# main_16.net
KiCad netlist of a schematic drawn in EAGLE
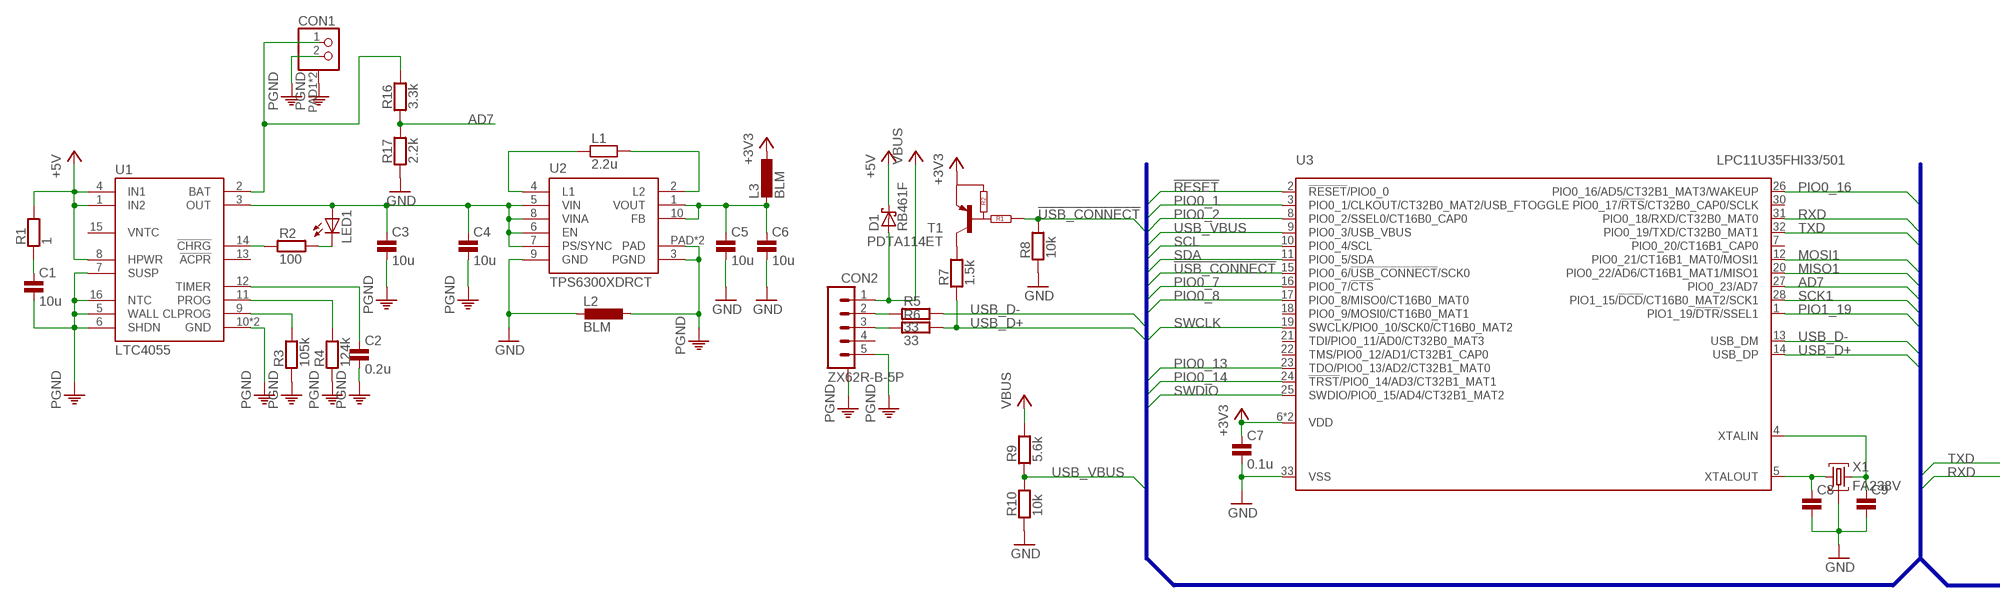
[diagram p0: schematic, sheet 1, part 1 of 2]
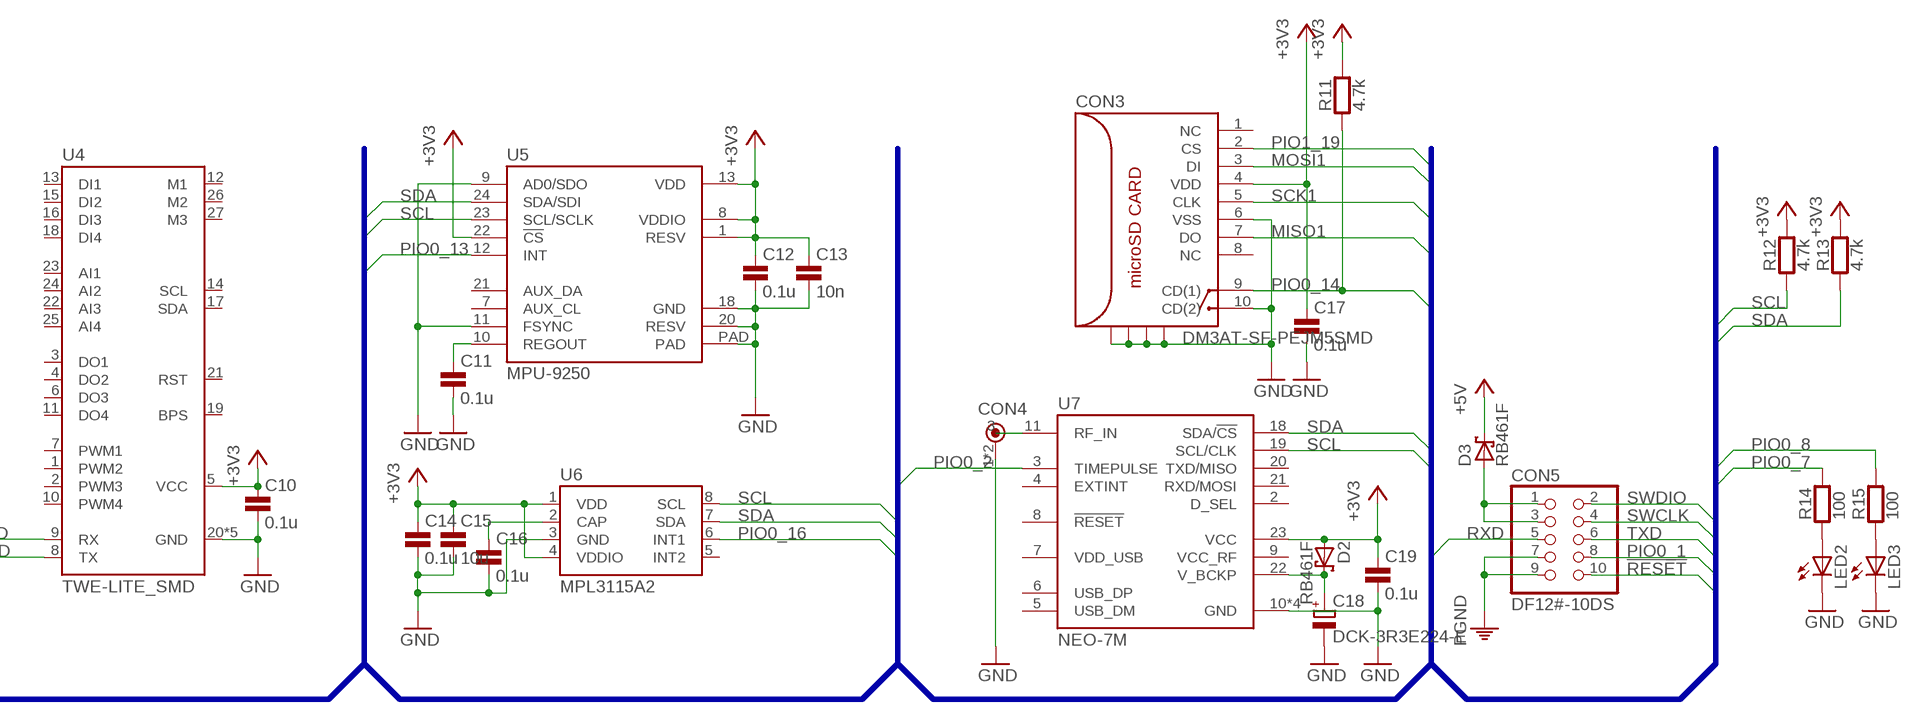
[diagram p1: schematic, sheet 1, part 2 of 2]

(export (version "E")
  (design (tool "Eeschema 10.0.6"))
  (components
    (comp (ref "C1")
      (value "10u")
      (footprint "eagle-import:0603")
      (libsource (lib "eagle-import") (part "C0603"))
    )
    (comp (ref "C2")
      (value "0.2u")
      (footprint "eagle-import:0402")
      (libsource (lib "eagle-import") (part "C0402"))
    )
    (comp (ref "C3")
      (value "10u")
      (footprint "eagle-import:0603")
      (libsource (lib "eagle-import") (part "C0603"))
    )
    (comp (ref "C4")
      (value "10u")
      (footprint "eagle-import:0603")
      (libsource (lib "eagle-import") (part "C0603"))
    )
    (comp (ref "C5")
      (value "10u")
      (footprint "eagle-import:0603")
      (libsource (lib "eagle-import") (part "C0603"))
    )
    (comp (ref "C6")
      (value "10u")
      (footprint "eagle-import:0603")
      (libsource (lib "eagle-import") (part "C0603"))
    )
    (comp (ref "C7")
      (value "0.1u")
      (footprint "eagle-import:0402")
      (libsource (lib "eagle-import") (part "C0402"))
    )
    (comp (ref "C8")
      (value "C0402")
      (footprint "eagle-import:0402")
      (libsource (lib "eagle-import") (part "C0402"))
    )
    (comp (ref "C9")
      (value "C0402")
      (footprint "eagle-import:0402")
      (libsource (lib "eagle-import") (part "C0402"))
    )
    (comp (ref "C10")
      (value "0.1u")
      (footprint "eagle-import:0402")
      (libsource (lib "eagle-import") (part "C0402"))
    )
    (comp (ref "C11")
      (value "0.1u")
      (footprint "eagle-import:0402")
      (libsource (lib "eagle-import") (part "C0402"))
    )
    (comp (ref "C12")
      (value "0.1u")
      (footprint "eagle-import:0402")
      (libsource (lib "eagle-import") (part "C0402"))
    )
    (comp (ref "C13")
      (value "10n")
      (footprint "eagle-import:0402")
      (libsource (lib "eagle-import") (part "C0402"))
    )
    (comp (ref "C14")
      (value "0.1u")
      (footprint "eagle-import:0402")
      (libsource (lib "eagle-import") (part "C0402"))
    )
    (comp (ref "C15")
      (value "10u")
      (footprint "eagle-import:0402")
      (libsource (lib "eagle-import") (part "C0402"))
    )
    (comp (ref "C16")
      (value "0.1u")
      (footprint "eagle-import:0402")
      (libsource (lib "eagle-import") (part "C0402"))
    )
    (comp (ref "C17")
      (value "0.1u")
      (footprint "eagle-import:0402")
      (libsource (lib "eagle-import") (part "C0402"))
    )
    (comp (ref "C18")
      (value "DCK-3R3E224-E")
      (footprint "eagle-import:DCK-3R3E224-E")
      (libsource (lib "eagle-import") (part "DCK-3R3E224-E"))
    )
    (comp (ref "C19")
      (value "0.1u")
      (footprint "eagle-import:0402")
      (libsource (lib "eagle-import") (part "C0402"))
    )
    (comp (ref "CON1")
      (value "JST-PH2")
      (footprint "eagle-import:JST-PH2")
      (libsource (lib "eagle-import") (part "JST-PH2"))
    )
    (comp (ref "CON2")
      (value "ZX62R-B-5P")
      (footprint "eagle-import:MICRO-B")
      (libsource (lib "eagle-import") (part "ZX62R-B-5P"))
    )
    (comp (ref "CON3")
      (value "DM3AT-SF-PEJM5SMD")
      (footprint "eagle-import:DM3AT-SF-PEJM5")
      (libsource (lib "eagle-import") (part "DM3AT-SF-PEJM5SMD"))
    )
    (comp (ref "CON4")
      (value "U.FL")
      (footprint "eagle-import:U.FL-R-SMT-1")
      (libsource (lib "eagle-import") (part "U.FL"))
    )
    (comp (ref "CON5")
      (value "DF12#-10DS")
      (footprint "eagle-import:DF12A-10DS")
      (libsource (lib "eagle-import") (part "DF12#-10DS"))
    )
    (comp (ref "D1")
      (value "RB461F")
      (footprint "eagle-import:UMD3")
      (libsource (lib "eagle-import") (part "RB461F"))
    )
    (comp (ref "D2")
      (value "RB461F")
      (footprint "eagle-import:UMD3")
      (libsource (lib "eagle-import") (part "RB461F"))
    )
    (comp (ref "D3")
      (value "RB461F")
      (footprint "eagle-import:UMD3")
      (libsource (lib "eagle-import") (part "RB461F"))
    )
    (comp (ref "L1")
      (value "2.2u")
      (footprint "eagle-import:VLF4012ST")
      (libsource (lib "eagle-import") (part "VLF4012ST"))
    )
    (comp (ref "L2")
      (value "BLM")
      (footprint "eagle-import:C0603K")
      (libsource (lib "eagle-import") (part "L-EU"))
    )
    (comp (ref "L3")
      (value "BLM")
      (footprint "eagle-import:C0603K")
      (libsource (lib "eagle-import") (part "L-EU"))
    )
    (comp (ref "LED1")
      (value "LEDSML0603")
      (footprint "eagle-import:SML0603")
      (libsource (lib "eagle-import") (part "LEDSML0603"))
    )
    (comp (ref "LED2")
      (value "LEDSML0603")
      (footprint "eagle-import:SML0603")
      (libsource (lib "eagle-import") (part "LEDSML0603"))
    )
    (comp (ref "LED3")
      (value "LEDSML0603")
      (footprint "eagle-import:SML0603")
      (libsource (lib "eagle-import") (part "LEDSML0603"))
    )
    (comp (ref "R1")
      (value "1")
      (footprint "eagle-import:0402")
      (libsource (lib "eagle-import") (part "R0402"))
    )
    (comp (ref "R2")
      (value "100")
      (footprint "eagle-import:0402")
      (libsource (lib "eagle-import") (part "R0402"))
    )
    (comp (ref "R3")
      (value "105k")
      (footprint "eagle-import:0402")
      (libsource (lib "eagle-import") (part "R0402"))
    )
    (comp (ref "R4")
      (value "124k")
      (footprint "eagle-import:0402")
      (libsource (lib "eagle-import") (part "R0402"))
    )
    (comp (ref "R5")
      (value "33")
      (footprint "eagle-import:0402")
      (libsource (lib "eagle-import") (part "R0402"))
    )
    (comp (ref "R6")
      (value "33")
      (footprint "eagle-import:0402")
      (libsource (lib "eagle-import") (part "R0402"))
    )
    (comp (ref "R7")
      (value "1.5k")
      (footprint "eagle-import:0402")
      (libsource (lib "eagle-import") (part "R0402"))
    )
    (comp (ref "R8")
      (value "10k")
      (footprint "eagle-import:0402")
      (libsource (lib "eagle-import") (part "R0402"))
    )
    (comp (ref "R9")
      (value "5.6k")
      (footprint "eagle-import:0402")
      (libsource (lib "eagle-import") (part "R0402"))
    )
    (comp (ref "R10")
      (value "10k")
      (footprint "eagle-import:0402")
      (libsource (lib "eagle-import") (part "R0402"))
    )
    (comp (ref "R11")
      (value "4.7k")
      (footprint "eagle-import:0402")
      (libsource (lib "eagle-import") (part "R0402"))
    )
    (comp (ref "R12")
      (value "4.7k")
      (footprint "eagle-import:0402")
      (libsource (lib "eagle-import") (part "R0402"))
    )
    (comp (ref "R13")
      (value "4.7k")
      (footprint "eagle-import:0402")
      (libsource (lib "eagle-import") (part "R0402"))
    )
    (comp (ref "R14")
      (value "100")
      (footprint "eagle-import:0402")
      (libsource (lib "eagle-import") (part "R0402"))
    )
    (comp (ref "R15")
      (value "100")
      (footprint "eagle-import:0402")
      (libsource (lib "eagle-import") (part "R0402"))
    )
    (comp (ref "R16")
      (value "3.3k")
      (footprint "eagle-import:0402")
      (libsource (lib "eagle-import") (part "R0402"))
    )
    (comp (ref "R17")
      (value "2.2k")
      (footprint "eagle-import:0402")
      (libsource (lib "eagle-import") (part "R0402"))
    )
    (comp (ref "T1")
      (value "PDTA114ET")
      (footprint "eagle-import:SOT23")
      (libsource (lib "eagle-import") (part "PDTA114TE"))
    )
    (comp (ref "U1")
      (value "LTC4055")
      (footprint "eagle-import:QFN16")
      (libsource (lib "eagle-import") (part "LTC4055"))
    )
    (comp (ref "U2")
      (value "TPS6300XDRCT")
      (footprint "eagle-import:S-PVSON-N10")
      (libsource (lib "eagle-import") (part "TPS6300XDRCT"))
    )
    (comp (ref "U3")
      (value "LPC11U35FHI33/501")
      (footprint "eagle-import:SOT617-3")
      (libsource (lib "eagle-import") (part "LPC11U35FHI33/501"))
    )
    (comp (ref "U4")
      (value "TWE-LITE_SMD")
      (footprint "eagle-import:LITE")
      (libsource (lib "eagle-import") (part "TWE-LITE_SMD"))
    )
    (comp (ref "U5")
      (value "MPU-9250")
      (footprint "eagle-import:MPU-9250")
      (libsource (lib "eagle-import") (part "MPU-9250"))
    )
    (comp (ref "U6")
      (value "MPL3115A2")
      (footprint "eagle-import:MPL3115A2")
      (libsource (lib "eagle-import") (part "MPL3115A2"))
    )
    (comp (ref "U7")
      (value "NEO-7M")
      (footprint "eagle-import:NEO-7M")
      (libsource (lib "eagle-import") (part "NEO-7M"))
    )
    (comp (ref "X1")
      (value "FA238V")
      (footprint "eagle-import:V66RA")
      (libsource (lib "eagle-import") (part "FA238V"))
    )
  )
  (nets
    (net (code "1") (name "+3V3") (class "Default")
      (node (ref "C10") (pin "1") (pinfunction "P$1_1") (pintype "passive"))
      (node (ref "C12") (pin "1") (pinfunction "P$1_1") (pintype "passive"))
      (node (ref "C13") (pin "1") (pinfunction "P$1_1") (pintype "passive"))
      (node (ref "C14") (pin "1") (pinfunction "P$1_1") (pintype "passive"))
      (node (ref "C15") (pin "1") (pinfunction "P$1_1") (pintype "passive"))
      (node (ref "C17") (pin "1") (pinfunction "P$1_1") (pintype "passive"))
      (node (ref "C19") (pin "1") (pinfunction "P$1_1") (pintype "passive"))
      (node (ref "C7") (pin "1") (pinfunction "P$1_1") (pintype "passive"))
      (node (ref "CON3") (pin "4") (pinfunction "VDD_4") (pintype "power_in"))
      (node (ref "D2") (pin "2") (pinfunction "A_2") (pintype "passive"))
      (node (ref "L3") (pin "1") (pinfunction "1_1") (pintype "passive"))
      (node (ref "R11") (pin "2") (pinfunction "P$2_2") (pintype "passive"))
      (node (ref "R12") (pin "2") (pinfunction "P$2_2") (pintype "passive"))
      (node (ref "R13") (pin "2") (pinfunction "P$2_2") (pintype "passive"))
      (node (ref "T1") (pin "2") (pinfunction "E_2") (pintype "passive"))
      (node (ref "U3") (pin "29") (pinfunction "VDD_29") (pintype "power_in"))
      (node (ref "U3") (pin "6") (pinfunction "VDD_6") (pintype "power_in"))
      (node (ref "U4") (pin "5") (pinfunction "VCC_5") (pintype "power_in"))
      (node (ref "U5") (pin "1") (pinfunction "RESV_1") (pintype "passive"))
      (node (ref "U5") (pin "13") (pinfunction "VDD_13") (pintype "power_in"))
      (node (ref "U5") (pin "22") (pinfunction "~{CS}_22") (pintype "input"))
      (node (ref "U5") (pin "8") (pinfunction "VDDIO_8") (pintype "power_in"))
      (node (ref "U6") (pin "1") (pinfunction "VDD_1") (pintype "power_in"))
      (node (ref "U6") (pin "4") (pinfunction "VDDIO_4") (pintype "input"))
      (node (ref "U7") (pin "23") (pinfunction "VCC_23") (pintype "power_in"))
    )
    (net (code "2") (name "+5V") (class "Default")
      (node (ref "D1") (pin "3") (pinfunction "C_3") (pintype "passive"))
      (node (ref "D3") (pin "3") (pinfunction "C_3") (pintype "passive"))
      (node (ref "R1") (pin "2") (pinfunction "P$2_2") (pintype "passive"))
      (node (ref "U1") (pin "1") (pinfunction "IN2_1") (pintype "power_in"))
      (node (ref "U1") (pin "4") (pinfunction "IN1_4") (pintype "power_in"))
      (node (ref "U1") (pin "8") (pinfunction "HPWR_8") (pintype "input"))
    )
    (net (code "3") (name "/AD7") (class "Default")
      (node (ref "R16") (pin "1") (pinfunction "P$1_1") (pintype "passive"))
      (node (ref "R17") (pin "2") (pinfunction "P$2_2") (pintype "passive"))
      (node (ref "U3") (pin "27") (pinfunction "PIO0_23/AD7_27") (pintype "bidirectional"))
    )
    (net (code "4") (name "/MISO1") (class "Default")
      (node (ref "CON3") (pin "7") (pinfunction "DO_7") (pintype "output"))
      (node (ref "U3") (pin "20") (pinfunction "PIO0_22/AD6/CT16B1_MAT1/MISO1_20") (pintype "bidirectional"))
    )
    (net (code "5") (name "/MOSI1") (class "Default")
      (node (ref "CON3") (pin "3") (pinfunction "DI_3") (pintype "input"))
      (node (ref "U3") (pin "12") (pinfunction "PIO0_21/CT16B1_MAT0/MOSI1_12") (pintype "bidirectional"))
    )
    (net (code "6") (name "/PIO0_1") (class "Default")
      (node (ref "CON5") (pin "8") (pinfunction "8_8") (pintype "passive"))
      (node (ref "U3") (pin "3") (pinfunction "PIO0_1/CLKOUT/CT32B0_MAT2/USB_FTOGGLE_3") (pintype "bidirectional"))
    )
    (net (code "7") (name "/PIO0_2") (class "Default")
      (node (ref "U3") (pin "8") (pinfunction "PIO0_2/SSEL0/CT16B0_CAP0_8") (pintype "bidirectional"))
      (node (ref "U7") (pin "3") (pinfunction "TIMEPULSE_3") (pintype "output"))
    )
    (net (code "8") (name "/PIO0_7") (class "Default")
      (node (ref "R14") (pin "2") (pinfunction "P$2_2") (pintype "passive"))
      (node (ref "U3") (pin "16") (pinfunction "PIO0_7/~{CTS}_16") (pintype "bidirectional"))
    )
    (net (code "9") (name "/PIO0_8") (class "Default")
      (node (ref "R15") (pin "2") (pinfunction "P$2_2") (pintype "passive"))
      (node (ref "U3") (pin "17") (pinfunction "PIO0_8/MISO0/CT16B0_MAT0_17") (pintype "bidirectional"))
    )
    (net (code "10") (name "/PIO0_13") (class "Default")
      (node (ref "U3") (pin "23") (pinfunction "TDO/PIO0_13/AD2/CT32B1_MAT0_23") (pintype "bidirectional"))
      (node (ref "U5") (pin "12") (pinfunction "INT_12") (pintype "output"))
    )
    (net (code "11") (name "/PIO0_14") (class "Default")
      (node (ref "CON3") (pin "9") (pinfunction "CD(1)_9") (pintype "bidirectional"))
      (node (ref "R11") (pin "1") (pinfunction "P$1_1") (pintype "passive"))
      (node (ref "U3") (pin "24") (pinfunction "~{TRST}/PIO0_14/AD3/CT32B1_MAT1_24") (pintype "bidirectional"))
    )
    (net (code "12") (name "/PIO0_16") (class "Default")
      (node (ref "U3") (pin "26") (pinfunction "PIO0_16/AD5/CT32B1_MAT3/WAKEUP_26") (pintype "bidirectional"))
      (node (ref "U6") (pin "6") (pinfunction "INT1_6") (pintype "output"))
    )
    (net (code "13") (name "/PIO1_19") (class "Default")
      (node (ref "CON3") (pin "2") (pinfunction "CS_2") (pintype "input"))
      (node (ref "U3") (pin "1") (pinfunction "PIO1_19/~{DTR}/SSEL1_1") (pintype "bidirectional"))
    )
    (net (code "14") (name "/RXD") (class "Default")
      (node (ref "CON5") (pin "5") (pinfunction "5_5") (pintype "passive"))
      (node (ref "U3") (pin "31") (pinfunction "PIO0_18/RXD/CT32B0_MAT0_31") (pintype "bidirectional"))
      (node (ref "U4") (pin "8") (pinfunction "TX_8") (pintype "output"))
    )
    (net (code "15") (name "/SCK1") (class "Default")
      (node (ref "CON3") (pin "5") (pinfunction "CLK_5") (pintype "input"))
      (node (ref "U3") (pin "28") (pinfunction "PIO1_15/~{DCD}/CT16B0_MAT2/SCK1_28") (pintype "bidirectional"))
    )
    (net (code "16") (name "/SCL") (class "Default")
      (node (ref "R12") (pin "1") (pinfunction "P$1_1") (pintype "passive"))
      (node (ref "U3") (pin "10") (pinfunction "PIO0_4/SCL_10") (pintype "bidirectional"))
      (node (ref "U5") (pin "23") (pinfunction "SCL/SCLK_23") (pintype "input"))
      (node (ref "U6") (pin "8") (pinfunction "SCL_8") (pintype "input"))
      (node (ref "U7") (pin "19") (pinfunction "SCL/CLK_19") (pintype "input"))
    )
    (net (code "17") (name "/SDA") (class "Default")
      (node (ref "R13") (pin "1") (pinfunction "P$1_1") (pintype "passive"))
      (node (ref "U3") (pin "11") (pinfunction "PIO0_5/SDA_11") (pintype "bidirectional"))
      (node (ref "U5") (pin "24") (pinfunction "SDA/SDI_24") (pintype "bidirectional"))
      (node (ref "U6") (pin "7") (pinfunction "SDA_7") (pintype "bidirectional"))
      (node (ref "U7") (pin "18") (pinfunction "SDA/~{CS}_18") (pintype "bidirectional"))
    )
    (net (code "18") (name "/SWCLK") (class "Default")
      (node (ref "CON5") (pin "4") (pinfunction "4_4") (pintype "passive"))
      (node (ref "U3") (pin "19") (pinfunction "SWCLK/PIO0_10/SCK0/CT16B0_MAT2_19") (pintype "bidirectional"))
    )
    (net (code "19") (name "/SWDIO") (class "Default")
      (node (ref "CON5") (pin "2") (pinfunction "2_2") (pintype "passive"))
      (node (ref "U3") (pin "25") (pinfunction "SWDIO/PIO0_15/AD4/CT32B1_MAT2_25") (pintype "bidirectional"))
    )
    (net (code "20") (name "/TXD") (class "Default")
      (node (ref "CON5") (pin "6") (pinfunction "6_6") (pintype "passive"))
      (node (ref "U3") (pin "32") (pinfunction "PIO0_19/TXD/CT32B0_MAT1_32") (pintype "bidirectional"))
      (node (ref "U4") (pin "9") (pinfunction "RX_9") (pintype "input"))
    )
    (net (code "21") (name "/USB_D+") (class "Default")
      (node (ref "R6") (pin "2") (pinfunction "P$2_2") (pintype "passive"))
      (node (ref "R7") (pin "1") (pinfunction "P$1_1") (pintype "passive"))
      (node (ref "U3") (pin "14") (pinfunction "USB_DP_14") (pintype "bidirectional"))
    )
    (net (code "22") (name "/USB_D-") (class "Default")
      (node (ref "R5") (pin "2") (pinfunction "P$2_2") (pintype "passive"))
      (node (ref "U3") (pin "13") (pinfunction "USB_DM_13") (pintype "bidirectional"))
    )
    (net (code "23") (name "/USB_VBUS") (class "Default")
      (node (ref "R10") (pin "2") (pinfunction "P$2_2") (pintype "passive"))
      (node (ref "R9") (pin "1") (pinfunction "P$1_1") (pintype "passive"))
      (node (ref "U3") (pin "9") (pinfunction "PIO0_3/USB_VBUS_9") (pintype "bidirectional"))
    )
    (net (code "24") (name "/VDD_USB") (class "Default")
      (node (ref "U7") (pin "7") (pinfunction "VDD_USB_7") (pintype "power_in"))
    )
    (net (code "25") (name "/VNTC") (class "Default")
      (node (ref "U1") (pin "15") (pinfunction "VNTC_15") (pintype "power_in"))
    )
    (net (code "26") (name "/~{RESET}") (class "Default")
      (node (ref "CON5") (pin "10") (pinfunction "10_10") (pintype "passive"))
      (node (ref "U3") (pin "2") (pinfunction "~{RESET}/PIO0_0_2") (pintype "bidirectional"))
    )
    (net (code "27") (name "/~{USB_CONNECT}") (class "Default")
      (node (ref "R8") (pin "2") (pinfunction "P$2_2") (pintype "passive"))
      (node (ref "T1") (pin "1") (pinfunction "INPUT_1") (pintype "passive"))
      (node (ref "U3") (pin "15") (pinfunction "PIO0_6/~{USB_CONNECT}/SCK0_15") (pintype "bidirectional"))
    )
    (net (code "28") (name "GND") (class "Default")
      (node (ref "C10") (pin "2") (pinfunction "P$2_2") (pintype "passive"))
      (node (ref "C11") (pin "2") (pinfunction "P$2_2") (pintype "passive"))
      (node (ref "C12") (pin "2") (pinfunction "P$2_2") (pintype "passive"))
      (node (ref "C13") (pin "2") (pinfunction "P$2_2") (pintype "passive"))
      (node (ref "C14") (pin "2") (pinfunction "P$2_2") (pintype "passive"))
      (node (ref "C15") (pin "2") (pinfunction "P$2_2") (pintype "passive"))
      (node (ref "C16") (pin "2") (pinfunction "P$2_2") (pintype "passive"))
      (node (ref "C17") (pin "2") (pinfunction "P$2_2") (pintype "passive"))
      (node (ref "C18") (pin "1") (pinfunction "-_1") (pintype "passive"))
      (node (ref "C19") (pin "2") (pinfunction "P$2_2") (pintype "passive"))
      (node (ref "C5") (pin "2") (pinfunction "P$2_2") (pintype "passive"))
      (node (ref "C6") (pin "2") (pinfunction "P$2_2") (pintype "passive"))
      (node (ref "C7") (pin "2") (pinfunction "P$2_2") (pintype "passive"))
      (node (ref "C8") (pin "2") (pinfunction "P$2_2") (pintype "passive"))
      (node (ref "C9") (pin "2") (pinfunction "P$2_2") (pintype "passive"))
      (node (ref "CON3") (pin "10") (pinfunction "CD(2)_10") (pintype "bidirectional"))
      (node (ref "CON3") (pin "6") (pinfunction "VSS_6") (pintype "power_in"))
      (node (ref "CON3") (pin "P$10") (pinfunction "P$1_P$10") (pintype "passive"))
      (node (ref "CON3") (pin "P$11") (pinfunction "P$2_P$11") (pintype "passive"))
      (node (ref "CON3") (pin "P$12") (pinfunction "P$3_P$12") (pintype "passive"))
      (node (ref "CON3") (pin "P$14") (pinfunction "P$4_P$14") (pintype "passive"))
      (node (ref "CON4") (pin "1") (pinfunction "GND_1") (pintype "power_in"))
      (node (ref "CON4") (pin "2") (pinfunction "GND_2") (pintype "power_in"))
      (node (ref "L2") (pin "2") (pinfunction "2_2") (pintype "passive"))
      (node (ref "LED2") (pin "C") (pinfunction "C_C") (pintype "passive"))
      (node (ref "LED3") (pin "C") (pinfunction "C_C") (pintype "passive"))
      (node (ref "R10") (pin "1") (pinfunction "P$1_1") (pintype "passive"))
      (node (ref "R17") (pin "1") (pinfunction "P$1_1") (pintype "passive"))
      (node (ref "R8") (pin "1") (pinfunction "P$1_1") (pintype "passive"))
      (node (ref "U2") (pin "9") (pinfunction "GND_9") (pintype "power_in"))
      (node (ref "U3") (pin "33") (pinfunction "VSS_33") (pintype "power_in"))
      (node (ref "U4") (pin "20") (pinfunction "GND_20") (pintype "power_in"))
      (node (ref "U4") (pin "28") (pinfunction "GND_28") (pintype "power_in"))
      (node (ref "U4") (pin "30") (pinfunction "GND_30") (pintype "power_in"))
      (node (ref "U4") (pin "31") (pinfunction "GND_31") (pintype "power_in"))
      (node (ref "U4") (pin "32") (pinfunction "GND_32") (pintype "power_in"))
      (node (ref "U5") (pin "11") (pinfunction "FSYNC_11") (pintype "input"))
      (node (ref "U5") (pin "18") (pinfunction "GND_18") (pintype "power_in"))
      (node (ref "U5") (pin "20") (pinfunction "RESV_20") (pintype "passive"))
      (node (ref "U5") (pin "9") (pinfunction "AD0/SDO_9") (pintype "bidirectional"))
      (node (ref "U5") (pin "PAD") (pinfunction "PAD_PAD") (pintype "passive"))
      (node (ref "U6") (pin "3") (pinfunction "GND_3") (pintype "power_in"))
      (node (ref "U7") (pin "10") (pinfunction "GND_10") (pintype "power_in"))
      (node (ref "U7") (pin "12") (pinfunction "GND_12") (pintype "power_in"))
      (node (ref "U7") (pin "13") (pinfunction "GND_13") (pintype "power_in"))
      (node (ref "U7") (pin "24") (pinfunction "GND_24") (pintype "power_in"))
      (node (ref "X1") (pin "P2GND") (pinfunction "GND_P2GND") (pintype "power_in"))
      (node (ref "X1") (pin "P4GND") (pinfunction "GND_P4GND") (pintype "power_in"))
    )
    (net (code "29") (name "Net-(C1-P$1)") (class "Default")
      (node (ref "C1") (pin "1") (pinfunction "P$1_1") (pintype "passive"))
      (node (ref "R1") (pin "1") (pinfunction "P$1_1") (pintype "passive"))
    )
    (net (code "30") (name "Net-(C2-P$1)") (class "Default")
      (node (ref "C2") (pin "1") (pinfunction "P$1_1") (pintype "passive"))
      (node (ref "U1") (pin "12") (pinfunction "TIMER_12") (pintype "passive"))
    )
    (net (code "31") (name "Net-(C3-P$1)") (class "Default")
      (node (ref "C3") (pin "1") (pinfunction "P$1_1") (pintype "passive"))
      (node (ref "C4") (pin "1") (pinfunction "P$1_1") (pintype "passive"))
      (node (ref "LED1") (pin "A") (pinfunction "A_A") (pintype "passive"))
      (node (ref "U1") (pin "3") (pinfunction "OUT_3") (pintype "power_in"))
      (node (ref "U2") (pin "5") (pinfunction "VIN_5") (pintype "power_in"))
      (node (ref "U2") (pin "6") (pinfunction "EN_6") (pintype "input"))
      (node (ref "U2") (pin "7") (pinfunction "PS/SYNC_7") (pintype "input"))
      (node (ref "U2") (pin "8") (pinfunction "VINA_8") (pintype "power_in"))
    )
    (net (code "32") (name "Net-(C5-P$1)") (class "Default")
      (node (ref "C5") (pin "1") (pinfunction "P$1_1") (pintype "passive"))
      (node (ref "C6") (pin "1") (pinfunction "P$1_1") (pintype "passive"))
      (node (ref "L3") (pin "2") (pinfunction "2_2") (pintype "passive"))
      (node (ref "U2") (pin "1") (pinfunction "VOUT_1") (pintype "output"))
      (node (ref "U2") (pin "10") (pinfunction "FB_10") (pintype "input"))
    )
    (net (code "33") (name "Net-(C8-P$1)") (class "Default")
      (node (ref "C8") (pin "1") (pinfunction "P$1_1") (pintype "passive"))
      (node (ref "U3") (pin "5") (pinfunction "XTALOUT_5") (pintype "output"))
      (node (ref "X1") (pin "P1X1") (pinfunction "X1_P1X1") (pintype "output"))
    )
    (net (code "34") (name "Net-(C9-P$1)") (class "Default")
      (node (ref "C9") (pin "1") (pinfunction "P$1_1") (pintype "passive"))
      (node (ref "U3") (pin "4") (pinfunction "XTALIN_4") (pintype "input"))
      (node (ref "X1") (pin "P3X2") (pinfunction "X2_P3X2") (pintype "output"))
    )
    (net (code "35") (name "Net-(C11-P$1)") (class "Default")
      (node (ref "C11") (pin "1") (pinfunction "P$1_1") (pintype "passive"))
      (node (ref "U5") (pin "10") (pinfunction "REGOUT_10") (pintype "passive"))
    )
    (net (code "36") (name "Net-(C16-P$1)") (class "Default")
      (node (ref "C16") (pin "1") (pinfunction "P$1_1") (pintype "passive"))
      (node (ref "U6") (pin "2") (pinfunction "CAP_2") (pintype "passive"))
    )
    (net (code "37") (name "Net-(C18-+)") (class "Default")
      (node (ref "C18") (pin "2") (pinfunction "+_2") (pintype "passive"))
      (node (ref "D2") (pin "3") (pinfunction "C_3") (pintype "passive"))
      (node (ref "U7") (pin "22") (pinfunction "V_BCKP_22") (pintype "power_in"))
    )
    (net (code "38") (name "Net-(CON2-2.D-)") (class "Default")
      (node (ref "CON2") (pin "2") (pinfunction "2.D-_2") (pintype "passive"))
      (node (ref "R5") (pin "1") (pinfunction "P$1_1") (pintype "passive"))
    )
    (net (code "39") (name "Net-(CON2-3.D+)") (class "Default")
      (node (ref "CON2") (pin "3") (pinfunction "3.D+_3") (pintype "passive"))
      (node (ref "R6") (pin "1") (pinfunction "P$1_1") (pintype "passive"))
    )
    (net (code "40") (name "Net-(CON4-RF)") (class "Default")
      (node (ref "CON4") (pin "3") (pinfunction "RF_3") (pintype "output"))
      (node (ref "U7") (pin "11") (pinfunction "RF_IN_11") (pintype "input"))
    )
    (net (code "41") (name "Net-(D3-A)") (class "Default")
      (node (ref "CON5") (pin "1") (pinfunction "1_1") (pintype "passive"))
      (node (ref "CON5") (pin "3") (pinfunction "3_3") (pintype "passive"))
      (node (ref "D3") (pin "2") (pinfunction "A_2") (pintype "passive"))
    )
    (net (code "42") (name "Net-(R2-P$1)") (class "Default")
      (node (ref "R2") (pin "1") (pinfunction "P$1_1") (pintype "passive"))
      (node (ref "U1") (pin "14") (pinfunction "~{CHRG}_14") (pintype "tri_state"))
    )
    (net (code "43") (name "Net-(R2-P$2)") (class "Default")
      (node (ref "LED1") (pin "C") (pinfunction "C_C") (pintype "passive"))
      (node (ref "R2") (pin "2") (pinfunction "P$2_2") (pintype "passive"))
    )
    (net (code "44") (name "Net-(R3-P$2)") (class "Default")
      (node (ref "R3") (pin "2") (pinfunction "P$2_2") (pintype "passive"))
      (node (ref "U1") (pin "9") (pinfunction "CLPROG_9") (pintype "passive"))
    )
    (net (code "45") (name "Net-(R4-P$2)") (class "Default")
      (node (ref "R4") (pin "2") (pinfunction "P$2_2") (pintype "passive"))
      (node (ref "U1") (pin "11") (pinfunction "PROG_11") (pintype "passive"))
    )
    (net (code "46") (name "Net-(R7-P$2)") (class "Default")
      (node (ref "R7") (pin "2") (pinfunction "P$2_2") (pintype "passive"))
      (node (ref "T1") (pin "3") (pinfunction "C_3") (pintype "passive"))
    )
    (net (code "47") (name "Net-(R14-P$1)") (class "Default")
      (node (ref "LED2") (pin "A") (pinfunction "A_A") (pintype "passive"))
      (node (ref "R14") (pin "1") (pinfunction "P$1_1") (pintype "passive"))
    )
    (net (code "48") (name "Net-(R15-P$1)") (class "Default")
      (node (ref "LED3") (pin "A") (pinfunction "A_A") (pintype "passive"))
      (node (ref "R15") (pin "1") (pinfunction "P$1_1") (pintype "passive"))
    )
    (net (code "49") (name "Net-(R16-P$2)") (class "Default")
      (node (ref "CON1") (pin "1") (pinfunction "1_1") (pintype "passive"))
      (node (ref "R16") (pin "2") (pinfunction "P$2_2") (pintype "passive"))
      (node (ref "U1") (pin "2") (pinfunction "BAT_2") (pintype "power_in"))
    )
    (net (code "50") (name "Net-(U2-L1)") (class "Default")
      (node (ref "L1") (pin "1") (pinfunction "1_1") (pintype "passive"))
      (node (ref "U2") (pin "4") (pinfunction "L1_4") (pintype "bidirectional"))
    )
    (net (code "51") (name "Net-(U2-L2)") (class "Default")
      (node (ref "L1") (pin "2") (pinfunction "2_2") (pintype "passive"))
      (node (ref "U2") (pin "2") (pinfunction "L2_2") (pintype "bidirectional"))
    )
    (net (code "52") (name "PGND") (class "Default")
      (node (ref "C1") (pin "2") (pinfunction "P$2_2") (pintype "passive"))
      (node (ref "C2") (pin "2") (pinfunction "P$2_2") (pintype "passive"))
      (node (ref "C3") (pin "2") (pinfunction "P$2_2") (pintype "passive"))
      (node (ref "C4") (pin "2") (pinfunction "P$2_2") (pintype "passive"))
      (node (ref "CON1") (pin "2") (pinfunction "2_2") (pintype "passive"))
      (node (ref "CON1") (pin "PAD1") (pinfunction "P$1_PAD1") (pintype "power_in"))
      (node (ref "CON1") (pin "PAD2") (pinfunction "P$1_PAD2") (pintype "power_in"))
      (node (ref "CON2") (pin "5") (pinfunction "5.GND_5") (pintype "passive"))
      (node (ref "CON2") (pin "CASE@1") (pinfunction "P$1_CASE@1") (pintype "bidirectional"))
      (node (ref "CON2") (pin "CASE@2") (pinfunction "P$1_CASE@2") (pintype "bidirectional"))
      (node (ref "CON2") (pin "CASE@3") (pinfunction "P$1_CASE@3") (pintype "bidirectional"))
      (node (ref "CON2") (pin "CASE@4") (pinfunction "P$1_CASE@4") (pintype "bidirectional"))
      (node (ref "CON5") (pin "7") (pinfunction "7_7") (pintype "passive"))
      (node (ref "CON5") (pin "9") (pinfunction "9_9") (pintype "passive"))
      (node (ref "L2") (pin "1") (pinfunction "1_1") (pintype "passive"))
      (node (ref "R3") (pin "1") (pinfunction "P$1_1") (pintype "passive"))
      (node (ref "R4") (pin "1") (pinfunction "P$1_1") (pintype "passive"))
      (node (ref "U1") (pin "10") (pinfunction "GND_10") (pintype "power_in"))
      (node (ref "U1") (pin "16") (pinfunction "NTC_16") (pintype "input"))
      (node (ref "U1") (pin "5") (pinfunction "WALL_5") (pintype "input"))
      (node (ref "U1") (pin "6") (pinfunction "SHDN_6") (pintype "input"))
      (node (ref "U1") (pin "7") (pinfunction "SUSP_7") (pintype "input"))
      (node (ref "U1") (pin "PAD") (pinfunction "GND_PAD") (pintype "power_in"))
      (node (ref "U2") (pin "3") (pinfunction "PGND_3") (pintype "power_in"))
      (node (ref "U2") (pin "PAD") (pinfunction "PAD_PAD") (pintype "power_in"))
      (node (ref "U2") (pin "PAD@1") (pinfunction "PAD_PAD@1") (pintype "power_in"))
    )
    (net (code "53") (name "VBUS") (class "Default")
      (node (ref "CON2") (pin "1") (pinfunction "1.VBUS_1") (pintype "passive"))
      (node (ref "D1") (pin "2") (pinfunction "A_2") (pintype "passive"))
      (node (ref "R9") (pin "2") (pinfunction "P$2_2") (pintype "passive"))
    )
    (net (code "54") (name "unconnected-(CON2-4.ID-Pad4)") (class "Default")
      (node (ref "CON2") (pin "4") (pinfunction "4.ID_4") (pintype "passive"))
    )
    (net (code "55") (name "unconnected-(CON3-NC-Pad1)") (class "Default")
      (node (ref "CON3") (pin "1") (pinfunction "NC_1") (pintype "no_connect"))
    )
    (net (code "56") (name "unconnected-(CON3-NC-Pad8)") (class "Default")
      (node (ref "CON3") (pin "8") (pinfunction "NC_8") (pintype "no_connect"))
    )
    (net (code "57") (name "unconnected-(U1-~{ACPR}-Pad13)") (class "Default")
      (node (ref "U1") (pin "13") (pinfunction "~{ACPR}_13") (pintype "tri_state"))
    )
    (net (code "58") (name "unconnected-(U3-PIO0_9{slash}MOSI0{slash}CT16B0_MAT1-Pad18)") (class "Default")
      (node (ref "U3") (pin "18") (pinfunction "PIO0_9/MOSI0/CT16B0_MAT1_18") (pintype "bidirectional"))
    )
    (net (code "59") (name "unconnected-(U3-PIO0_17{slash}~{RTS}{slash}CT32B0_CAP0{slash}SCLK-Pad30)") (class "Default")
      (node (ref "U3") (pin "30") (pinfunction "PIO0_17/~{RTS}/CT32B0_CAP0/SCLK_30") (pintype "bidirectional"))
    )
    (net (code "60") (name "unconnected-(U3-PIO0_20{slash}CT16B1_CAP0-Pad7)") (class "Default")
      (node (ref "U3") (pin "7") (pinfunction "PIO0_20/CT16B1_CAP0_7") (pintype "bidirectional"))
    )
    (net (code "61") (name "unconnected-(U3-TDI{slash}PIO0_11{slash}AD0{slash}CT32B0_MAT3-Pad21)") (class "Default")
      (node (ref "U3") (pin "21") (pinfunction "TDI/PIO0_11/AD0/CT32B0_MAT3_21") (pintype "bidirectional"))
    )
    (net (code "62") (name "unconnected-(U3-TMS{slash}PIO0_12{slash}AD1{slash}CT32B1_CAP0-Pad22)") (class "Default")
      (node (ref "U3") (pin "22") (pinfunction "TMS/PIO0_12/AD1/CT32B1_CAP0_22") (pintype "bidirectional"))
    )
    (net (code "63") (name "unconnected-(U4-AI1-Pad23)") (class "Default")
      (node (ref "U4") (pin "23") (pinfunction "AI1_23") (pintype "input"))
    )
    (net (code "64") (name "unconnected-(U4-AI2-Pad24)") (class "Default")
      (node (ref "U4") (pin "24") (pinfunction "AI2_24") (pintype "input"))
    )
    (net (code "65") (name "unconnected-(U4-AI3-Pad22)") (class "Default")
      (node (ref "U4") (pin "22") (pinfunction "AI3_22") (pintype "input"))
    )
    (net (code "66") (name "unconnected-(U4-AI4-Pad25)") (class "Default")
      (node (ref "U4") (pin "25") (pinfunction "AI4_25") (pintype "input"))
    )
    (net (code "67") (name "unconnected-(U4-BPS-Pad19)") (class "Default")
      (node (ref "U4") (pin "19") (pinfunction "BPS_19") (pintype "input"))
    )
    (net (code "68") (name "unconnected-(U4-DI1-Pad13)") (class "Default")
      (node (ref "U4") (pin "13") (pinfunction "DI1_13") (pintype "input"))
    )
    (net (code "69") (name "unconnected-(U4-DI2-Pad15)") (class "Default")
      (node (ref "U4") (pin "15") (pinfunction "DI2_15") (pintype "input"))
    )
    (net (code "70") (name "unconnected-(U4-DI3-Pad16)") (class "Default")
      (node (ref "U4") (pin "16") (pinfunction "DI3_16") (pintype "input"))
    )
    (net (code "71") (name "unconnected-(U4-DI4-Pad18)") (class "Default")
      (node (ref "U4") (pin "18") (pinfunction "DI4_18") (pintype "input"))
    )
    (net (code "72") (name "unconnected-(U4-DO1-Pad3)") (class "Default")
      (node (ref "U4") (pin "3") (pinfunction "DO1_3") (pintype "output"))
    )
    (net (code "73") (name "unconnected-(U4-DO2-Pad4)") (class "Default")
      (node (ref "U4") (pin "4") (pinfunction "DO2_4") (pintype "output"))
    )
    (net (code "74") (name "unconnected-(U4-DO3-Pad6)") (class "Default")
      (node (ref "U4") (pin "6") (pinfunction "DO3_6") (pintype "output"))
    )
    (net (code "75") (name "unconnected-(U4-DO4-Pad11)") (class "Default")
      (node (ref "U4") (pin "11") (pinfunction "DO4_11") (pintype "output"))
    )
    (net (code "76") (name "unconnected-(U4-M1-Pad12)") (class "Default")
      (node (ref "U4") (pin "12") (pinfunction "M1_12") (pintype "input"))
    )
    (net (code "77") (name "unconnected-(U4-M2-Pad26)") (class "Default")
      (node (ref "U4") (pin "26") (pinfunction "M2_26") (pintype "input"))
    )
    (net (code "78") (name "unconnected-(U4-M3-Pad27)") (class "Default")
      (node (ref "U4") (pin "27") (pinfunction "M3_27") (pintype "input"))
    )
    (net (code "79") (name "unconnected-(U4-PWM1-Pad7)") (class "Default")
      (node (ref "U4") (pin "7") (pinfunction "PWM1_7") (pintype "output"))
    )
    (net (code "80") (name "unconnected-(U4-PWM2-Pad1)") (class "Default")
      (node (ref "U4") (pin "1") (pinfunction "PWM2_1") (pintype "output"))
    )
    (net (code "81") (name "unconnected-(U4-PWM3-Pad2)") (class "Default")
      (node (ref "U4") (pin "2") (pinfunction "PWM3_2") (pintype "output"))
    )
    (net (code "82") (name "unconnected-(U4-PWM4-Pad10)") (class "Default")
      (node (ref "U4") (pin "10") (pinfunction "PWM4_10") (pintype "output"))
    )
    (net (code "83") (name "unconnected-(U4-RST-Pad21)") (class "Default")
      (node (ref "U4") (pin "21") (pinfunction "RST_21") (pintype "input"))
    )
    (net (code "84") (name "unconnected-(U4-SCL-Pad14)") (class "Default")
      (node (ref "U4") (pin "14") (pinfunction "SCL_14") (pintype "bidirectional"))
    )
    (net (code "85") (name "unconnected-(U4-SDA-Pad17)") (class "Default")
      (node (ref "U4") (pin "17") (pinfunction "SDA_17") (pintype "bidirectional"))
    )
    (net (code "86") (name "unconnected-(U5-AUX_CL-Pad7)") (class "Default")
      (node (ref "U5") (pin "7") (pinfunction "AUX_CL_7") (pintype "output"))
    )
    (net (code "87") (name "unconnected-(U5-AUX_DA-Pad21)") (class "Default")
      (node (ref "U5") (pin "21") (pinfunction "AUX_DA_21") (pintype "bidirectional"))
    )
    (net (code "88") (name "unconnected-(U6-INT2-Pad5)") (class "Default")
      (node (ref "U6") (pin "5") (pinfunction "INT2_5") (pintype "output"))
    )
    (net (code "89") (name "unconnected-(U7-D_SEL-Pad2)") (class "Default")
      (node (ref "U7") (pin "2") (pinfunction "D_SEL_2") (pintype "input"))
    )
    (net (code "90") (name "unconnected-(U7-EXTINT-Pad4)") (class "Default")
      (node (ref "U7") (pin "4") (pinfunction "EXTINT_4") (pintype "input"))
    )
    (net (code "91") (name "unconnected-(U7-RXD{slash}MOSI-Pad21)") (class "Default")
      (node (ref "U7") (pin "21") (pinfunction "RXD/MOSI_21") (pintype "input"))
    )
    (net (code "92") (name "unconnected-(U7-TXD{slash}MISO-Pad20)") (class "Default")
      (node (ref "U7") (pin "20") (pinfunction "TXD/MISO_20") (pintype "output"))
    )
    (net (code "93") (name "unconnected-(U7-USB_DM-Pad5)") (class "Default")
      (node (ref "U7") (pin "5") (pinfunction "USB_DM_5") (pintype "bidirectional"))
    )
    (net (code "94") (name "unconnected-(U7-USB_DP-Pad6)") (class "Default")
      (node (ref "U7") (pin "6") (pinfunction "USB_DP_6") (pintype "bidirectional"))
    )
    (net (code "95") (name "unconnected-(U7-VCC_RF-Pad9)") (class "Default")
      (node (ref "U7") (pin "9") (pinfunction "VCC_RF_9") (pintype "input"))
    )
    (net (code "96") (name "unconnected-(U7-~{RESET}-Pad8)") (class "Default")
      (node (ref "U7") (pin "8") (pinfunction "~{RESET}_8") (pintype "input"))
    )
  )
)
